# RW_CAN.net
KiCad netlist of a schematic drawn in EAGLE
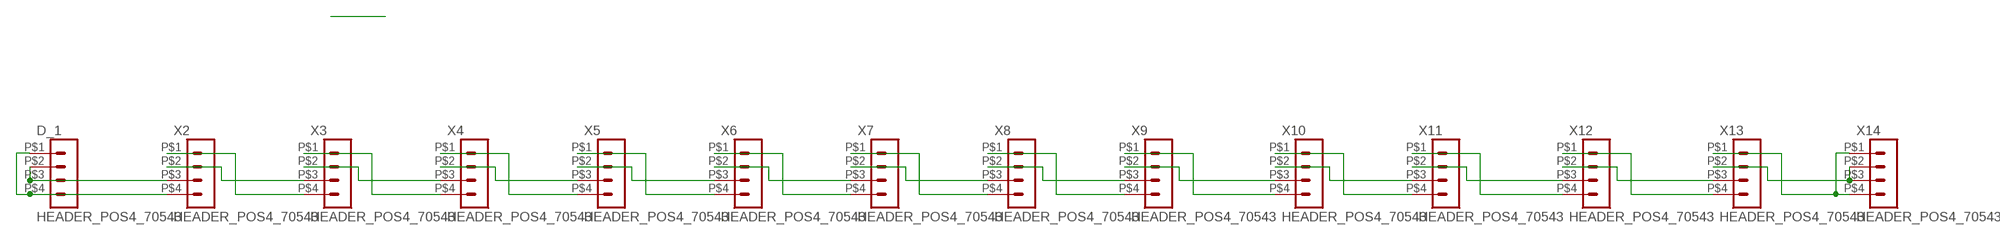
[diagram p0: schematic, sheet 1]

(export (version "E")
  (design (tool "Eeschema 10.0.6"))
  (components
    (comp (ref "D_1")
      (value "HEADER_POS4_70543")
      (footprint "eagle-import:70543-POS4")
      (libsource (lib "eagle-import") (part "HEADER_POS4_?70543"))
    )
    (comp (ref "X2")
      (value "HEADER_POS4_70543")
      (footprint "eagle-import:70543-POS4")
      (libsource (lib "eagle-import") (part "HEADER_POS4_?70543"))
    )
    (comp (ref "X3")
      (value "HEADER_POS4_70543")
      (footprint "eagle-import:70543-POS4")
      (libsource (lib "eagle-import") (part "HEADER_POS4_?70543"))
    )
    (comp (ref "X4")
      (value "HEADER_POS4_70543")
      (footprint "eagle-import:70543-POS4")
      (libsource (lib "eagle-import") (part "HEADER_POS4_?70543"))
    )
    (comp (ref "X5")
      (value "HEADER_POS4_70543")
      (footprint "eagle-import:70543-POS4")
      (libsource (lib "eagle-import") (part "HEADER_POS4_?70543"))
    )
    (comp (ref "X6")
      (value "HEADER_POS4_70543")
      (footprint "eagle-import:70543-POS4")
      (libsource (lib "eagle-import") (part "HEADER_POS4_?70543"))
    )
    (comp (ref "X7")
      (value "HEADER_POS4_70543")
      (footprint "eagle-import:70543-POS4")
      (libsource (lib "eagle-import") (part "HEADER_POS4_?70543"))
    )
    (comp (ref "X8")
      (value "HEADER_POS4_70543")
      (footprint "eagle-import:70543-POS4")
      (libsource (lib "eagle-import") (part "HEADER_POS4_?70543"))
    )
    (comp (ref "X9")
      (value "HEADER_POS4_70543")
      (footprint "eagle-import:70543-POS4")
      (libsource (lib "eagle-import") (part "HEADER_POS4_?70543"))
    )
    (comp (ref "X10")
      (value "HEADER_POS4_70543")
      (footprint "eagle-import:70543-POS4")
      (libsource (lib "eagle-import") (part "HEADER_POS4_?70543"))
    )
    (comp (ref "X11")
      (value "HEADER_POS4_70543")
      (footprint "eagle-import:70543-POS4")
      (libsource (lib "eagle-import") (part "HEADER_POS4_?70543"))
    )
    (comp (ref "X12")
      (value "HEADER_POS4_70543")
      (footprint "eagle-import:70543-POS4")
      (libsource (lib "eagle-import") (part "HEADER_POS4_?70543"))
    )
    (comp (ref "X13")
      (value "HEADER_POS4_70543")
      (footprint "eagle-import:70543-POS4")
      (libsource (lib "eagle-import") (part "HEADER_POS4_?70543"))
    )
    (comp (ref "X14")
      (value "HEADER_POS4_70543")
      (footprint "eagle-import:70543-POS4")
      (libsource (lib "eagle-import") (part "HEADER_POS4_?70543"))
    )
  )
  (nets
    (net (code "1") (name "Net-(D_1-1)") (class "Default")
      (node (ref "D_1") (pin "P$1") (pinfunction "1_P$1") (pintype "passive"))
      (node (ref "D_1") (pin "P$4") (pinfunction "4_P$4") (pintype "passive"))
      (node (ref "X2") (pin "P$4") (pinfunction "4_P$4") (pintype "passive"))
    )
    (net (code "2") (name "Net-(D_1-2)") (class "Default")
      (node (ref "D_1") (pin "P$2") (pinfunction "2_P$2") (pintype "passive"))
      (node (ref "D_1") (pin "P$3") (pinfunction "3_P$3") (pintype "passive"))
      (node (ref "X2") (pin "P$3") (pinfunction "3_P$3") (pintype "passive"))
    )
    (net (code "3") (name "Net-(X2-1)") (class "Default")
      (node (ref "X2") (pin "P$1") (pinfunction "1_P$1") (pintype "passive"))
      (node (ref "X3") (pin "P$4") (pinfunction "4_P$4") (pintype "passive"))
    )
    (net (code "4") (name "Net-(X2-2)") (class "Default")
      (node (ref "X2") (pin "P$2") (pinfunction "2_P$2") (pintype "passive"))
      (node (ref "X3") (pin "P$3") (pinfunction "3_P$3") (pintype "passive"))
    )
    (net (code "5") (name "Net-(X3-1)") (class "Default")
      (node (ref "X3") (pin "P$1") (pinfunction "1_P$1") (pintype "passive"))
      (node (ref "X4") (pin "P$4") (pinfunction "4_P$4") (pintype "passive"))
    )
    (net (code "6") (name "Net-(X3-2)") (class "Default")
      (node (ref "X3") (pin "P$2") (pinfunction "2_P$2") (pintype "passive"))
      (node (ref "X4") (pin "P$3") (pinfunction "3_P$3") (pintype "passive"))
    )
    (net (code "7") (name "Net-(X4-1)") (class "Default")
      (node (ref "X4") (pin "P$1") (pinfunction "1_P$1") (pintype "passive"))
      (node (ref "X5") (pin "P$4") (pinfunction "4_P$4") (pintype "passive"))
    )
    (net (code "8") (name "Net-(X4-2)") (class "Default")
      (node (ref "X4") (pin "P$2") (pinfunction "2_P$2") (pintype "passive"))
      (node (ref "X5") (pin "P$3") (pinfunction "3_P$3") (pintype "passive"))
    )
    (net (code "9") (name "Net-(X5-1)") (class "Default")
      (node (ref "X5") (pin "P$1") (pinfunction "1_P$1") (pintype "passive"))
      (node (ref "X6") (pin "P$4") (pinfunction "4_P$4") (pintype "passive"))
    )
    (net (code "10") (name "Net-(X5-2)") (class "Default")
      (node (ref "X5") (pin "P$2") (pinfunction "2_P$2") (pintype "passive"))
      (node (ref "X6") (pin "P$3") (pinfunction "3_P$3") (pintype "passive"))
    )
    (net (code "11") (name "Net-(X6-1)") (class "Default")
      (node (ref "X6") (pin "P$1") (pinfunction "1_P$1") (pintype "passive"))
      (node (ref "X7") (pin "P$4") (pinfunction "4_P$4") (pintype "passive"))
    )
    (net (code "12") (name "Net-(X6-2)") (class "Default")
      (node (ref "X6") (pin "P$2") (pinfunction "2_P$2") (pintype "passive"))
      (node (ref "X7") (pin "P$3") (pinfunction "3_P$3") (pintype "passive"))
    )
    (net (code "13") (name "Net-(X7-1)") (class "Default")
      (node (ref "X7") (pin "P$1") (pinfunction "1_P$1") (pintype "passive"))
      (node (ref "X8") (pin "P$4") (pinfunction "4_P$4") (pintype "passive"))
    )
    (net (code "14") (name "Net-(X7-2)") (class "Default")
      (node (ref "X7") (pin "P$2") (pinfunction "2_P$2") (pintype "passive"))
      (node (ref "X8") (pin "P$3") (pinfunction "3_P$3") (pintype "passive"))
    )
    (net (code "15") (name "Net-(X8-1)") (class "Default")
      (node (ref "X8") (pin "P$1") (pinfunction "1_P$1") (pintype "passive"))
      (node (ref "X9") (pin "P$4") (pinfunction "4_P$4") (pintype "passive"))
    )
    (net (code "16") (name "Net-(X8-2)") (class "Default")
      (node (ref "X8") (pin "P$2") (pinfunction "2_P$2") (pintype "passive"))
      (node (ref "X9") (pin "P$3") (pinfunction "3_P$3") (pintype "passive"))
    )
    (net (code "17") (name "Net-(X10-1)") (class "Default")
      (node (ref "X10") (pin "P$1") (pinfunction "1_P$1") (pintype "passive"))
      (node (ref "X11") (pin "P$4") (pinfunction "4_P$4") (pintype "passive"))
    )
    (net (code "18") (name "Net-(X10-2)") (class "Default")
      (node (ref "X10") (pin "P$2") (pinfunction "2_P$2") (pintype "passive"))
      (node (ref "X11") (pin "P$3") (pinfunction "3_P$3") (pintype "passive"))
    )
    (net (code "19") (name "Net-(X10-3)") (class "Default")
      (node (ref "X10") (pin "P$3") (pinfunction "3_P$3") (pintype "passive"))
      (node (ref "X9") (pin "P$2") (pinfunction "2_P$2") (pintype "passive"))
    )
    (net (code "20") (name "Net-(X10-4)") (class "Default")
      (node (ref "X10") (pin "P$4") (pinfunction "4_P$4") (pintype "passive"))
      (node (ref "X9") (pin "P$1") (pinfunction "1_P$1") (pintype "passive"))
    )
    (net (code "21") (name "Net-(X11-1)") (class "Default")
      (node (ref "X11") (pin "P$1") (pinfunction "1_P$1") (pintype "passive"))
      (node (ref "X12") (pin "P$4") (pinfunction "4_P$4") (pintype "passive"))
    )
    (net (code "22") (name "Net-(X11-2)") (class "Default")
      (node (ref "X11") (pin "P$2") (pinfunction "2_P$2") (pintype "passive"))
      (node (ref "X12") (pin "P$3") (pinfunction "3_P$3") (pintype "passive"))
    )
    (net (code "23") (name "Net-(X12-1)") (class "Default")
      (node (ref "X12") (pin "P$1") (pinfunction "1_P$1") (pintype "passive"))
      (node (ref "X13") (pin "P$4") (pinfunction "4_P$4") (pintype "passive"))
    )
    (net (code "24") (name "Net-(X12-2)") (class "Default")
      (node (ref "X12") (pin "P$2") (pinfunction "2_P$2") (pintype "passive"))
      (node (ref "X13") (pin "P$3") (pinfunction "3_P$3") (pintype "passive"))
    )
    (net (code "25") (name "Net-(X13-1)") (class "Default")
      (node (ref "X13") (pin "P$1") (pinfunction "1_P$1") (pintype "passive"))
      (node (ref "X14") (pin "P$1") (pinfunction "1_P$1") (pintype "passive"))
      (node (ref "X14") (pin "P$4") (pinfunction "4_P$4") (pintype "passive"))
    )
    (net (code "26") (name "Net-(X13-2)") (class "Default")
      (node (ref "X13") (pin "P$2") (pinfunction "2_P$2") (pintype "passive"))
      (node (ref "X14") (pin "P$2") (pinfunction "2_P$2") (pintype "passive"))
      (node (ref "X14") (pin "P$3") (pinfunction "3_P$3") (pintype "passive"))
    )
  )
)
